# TempSense.net
KiCad netlist of a schematic drawn in Altium Designer
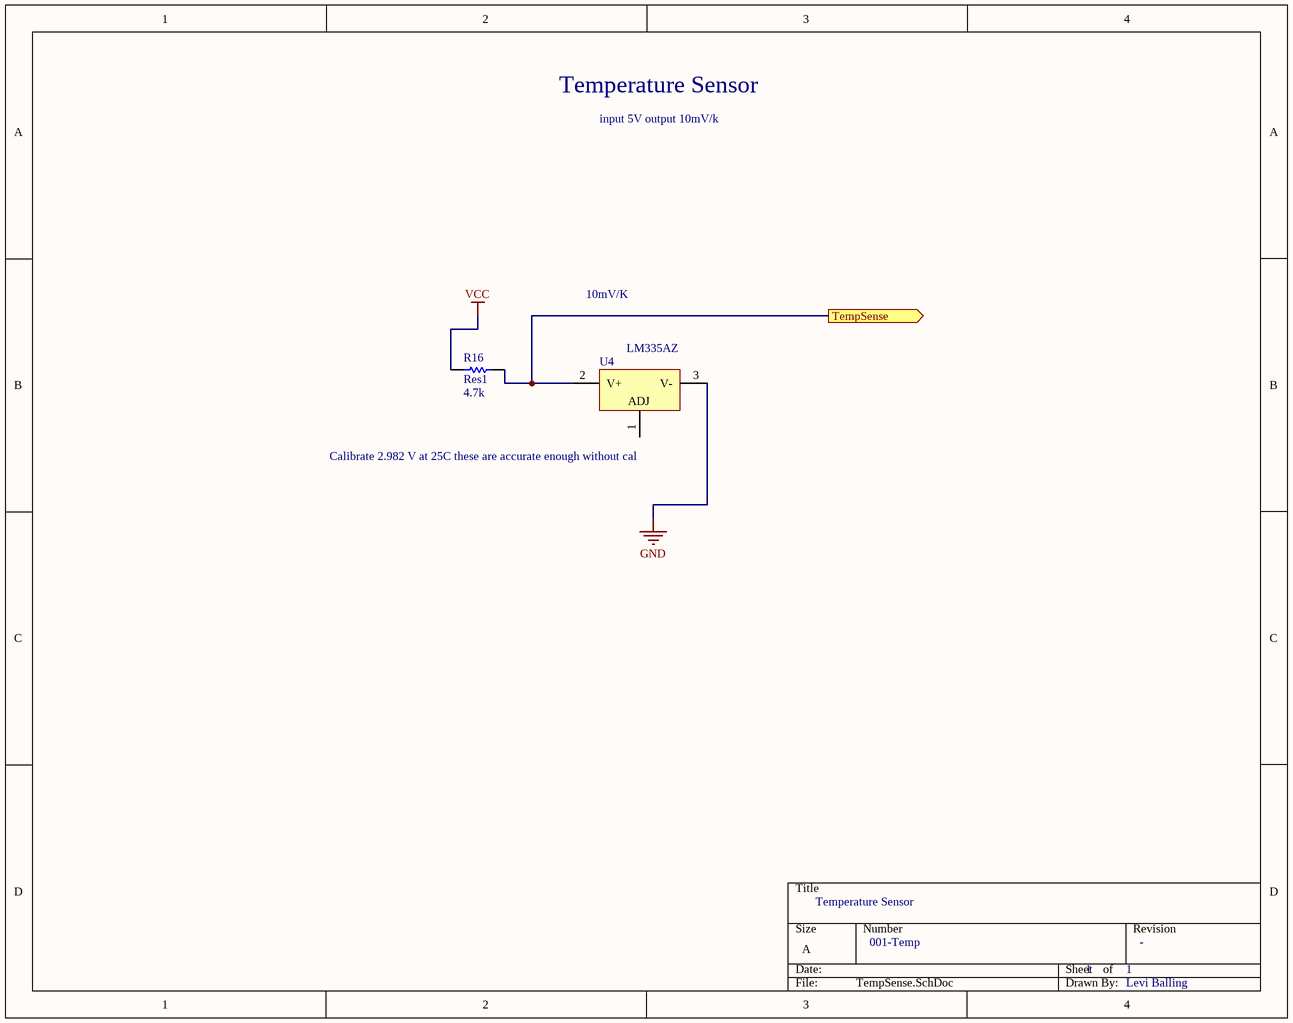
[diagram p0: TempSense.SchDoc]

(export (version "E")
  (design (tool "Eeschema 10.0.6"))
  (components
    (comp (ref "R16")
      (value "Res1")
      (footprint "AXIAL-0.3")
      (description "Resistor")
      (fields (field (name "ALTIUM_VALUE") "4.7k") (field (name "PUBLISHER") "Altium Limited"))
      (libsource (lib "Miscellaneous Devices") (part "Res1"))
    )
    (comp (ref "U4")
      (value "LM335AZ")
      (footprint "Z03A")
      (description "Precision Temperature Sensor")
      (fields
        (field (name "MANUFACTURER") "National Semiconductor")
        (field (name "DIGIKEYPARTNUMBER") "LM335AZ-ND")
        (field (name "PUBLISHER") "Altium Limited")
      )
      (libsource (lib "NSC Temperature Sensor") (part "LM335AZ"))
    )
  )
  (nets
    (net (code "1") (name "/TempSense") (class "Default")
      (node (ref "R16") (pin "2") (pinfunction "2_2") (pintype "passive"))
      (node (ref "U4") (pin "2") (pinfunction "V+_2") (pintype "passive"))
    )
    (net (code "2") (name "GND") (class "Default")
      (node (ref "U4") (pin "3") (pinfunction "V-_3") (pintype "passive"))
    )
    (net (code "3") (name "VCC") (class "Default")
      (node (ref "R16") (pin "1") (pinfunction "1_1") (pintype "passive"))
    )
    (net (code "4") (name "unconnected-(U4-ADJ-Pad1)") (class "Default")
      (node (ref "U4") (pin "1") (pinfunction "ADJ_1") (pintype "passive"))
    )
  )
)
